# TMC2100_BOB_v0_90.net
KiCad netlist of a schematic drawn in EAGLE
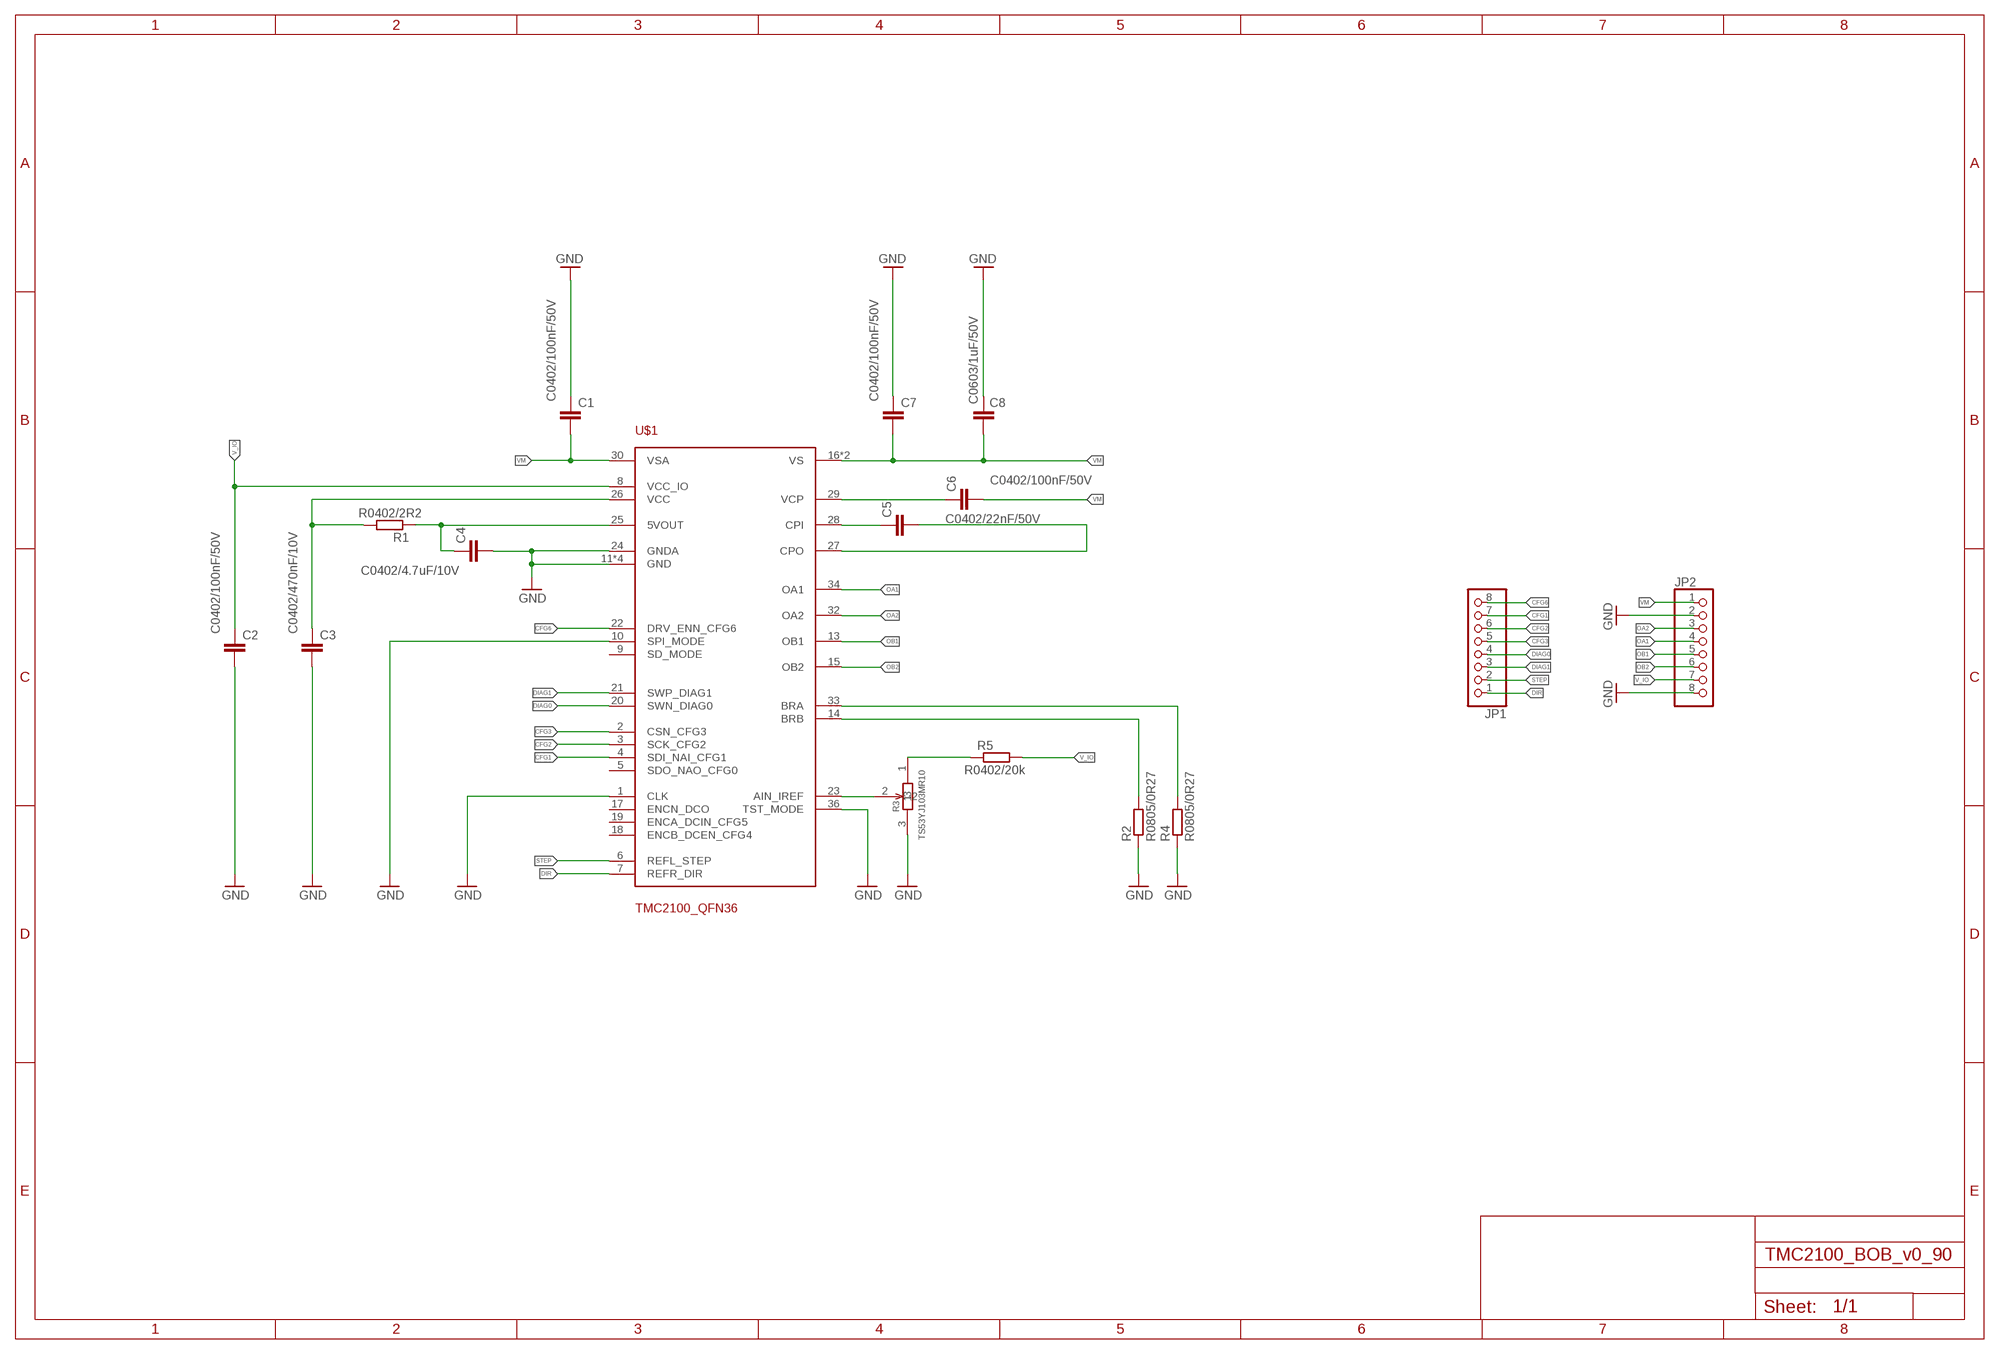
[diagram p0: schematic, sheet 1]

(export (version "E")
  (design (tool "Eeschema 10.0.6"))
  (components
    (comp (ref "C1")
      (value "C0402/100nF/50V")
      (footprint "eagle-import:C0402")
      (libsource (lib "eagle-import") (part "C-EUC0402"))
    )
    (comp (ref "C2")
      (value "C0402/100nF/50V")
      (footprint "eagle-import:C0402")
      (libsource (lib "eagle-import") (part "C-EUC0402"))
    )
    (comp (ref "C3")
      (value "C0402/470nF/10V")
      (footprint "eagle-import:C0402")
      (libsource (lib "eagle-import") (part "C-EUC0402"))
    )
    (comp (ref "C4")
      (value "C0402/4.7uF/10V")
      (footprint "eagle-import:C0402")
      (libsource (lib "eagle-import") (part "C-EUC0402"))
    )
    (comp (ref "C5")
      (value "C0402/22nF/50V")
      (footprint "eagle-import:C0402")
      (libsource (lib "eagle-import") (part "C-EUC0402"))
    )
    (comp (ref "C6")
      (value "C0402/100nF/50V")
      (footprint "eagle-import:C0402")
      (libsource (lib "eagle-import") (part "C-EUC0402"))
    )
    (comp (ref "C7")
      (value "C0402/100nF/50V")
      (footprint "eagle-import:C0402")
      (libsource (lib "eagle-import") (part "C-EUC0402"))
    )
    (comp (ref "C8")
      (value "C0603/1uF/50V")
      (footprint "eagle-import:C0603")
      (libsource (lib "eagle-import") (part "C-EUC0603"))
    )
    (comp (ref "JP1")
      (value "PINHD-1X08_2.54-S")
      (footprint "eagle-import:1X08-S")
      (libsource (lib "eagle-import") (part "PINHD-1X08_2.54-S"))
    )
    (comp (ref "JP2")
      (value "PINHD-1X08_2.54-S")
      (footprint "eagle-import:1X08-S")
      (libsource (lib "eagle-import") (part "PINHD-1X08_2.54-S"))
    )
    (comp (ref "R1")
      (value "R0402/2R2")
      (footprint "eagle-import:R0402")
      (libsource (lib "eagle-import") (part "R-EU_R0402"))
    )
    (comp (ref "R2")
      (value "R0805/0R27")
      (footprint "eagle-import:M0805")
      (libsource (lib "eagle-import") (part "R-EU_M0805"))
    )
    (comp (ref "R3")
      (value "TS53YJ103MR10")
      (footprint "eagle-import:TS53YJ")
      (libsource (lib "eagle-import") (part "TS53YJ103MR10"))
    )
    (comp (ref "R4")
      (value "R0805/0R27")
      (footprint "eagle-import:M0805")
      (libsource (lib "eagle-import") (part "R-EU_M0805"))
    )
    (comp (ref "R5")
      (value "R0402/20k")
      (footprint "eagle-import:R0402")
      (libsource (lib "eagle-import") (part "R-EU_R0402"))
    )
    (comp (ref "U$1")
      (value "TMC2100_QFN36")
      (footprint "eagle-import:QFN36")
      (libsource (lib "eagle-import") (part "TMC2100_QFN36"))
    )
  )
  (nets
    (net (code "1") (name "CFG1") (class "Default")
      (node (ref "JP1") (pin "7") (pinfunction "7_7") (pintype "passive"))
      (node (ref "U$1") (pin "4") (pinfunction "SDI_NAI_CFG1_4") (pintype "bidirectional"))
    )
    (net (code "2") (name "CFG2") (class "Default")
      (node (ref "JP1") (pin "6") (pinfunction "6_6") (pintype "passive"))
      (node (ref "U$1") (pin "3") (pinfunction "SCK_CFG2_3") (pintype "bidirectional"))
    )
    (net (code "3") (name "CFG3") (class "Default")
      (node (ref "JP1") (pin "5") (pinfunction "5_5") (pintype "passive"))
      (node (ref "U$1") (pin "2") (pinfunction "CSN_CFG3_2") (pintype "bidirectional"))
    )
    (net (code "4") (name "CFG6") (class "Default")
      (node (ref "JP1") (pin "8") (pinfunction "8_8") (pintype "passive"))
      (node (ref "U$1") (pin "22") (pinfunction "DRV_ENN_CFG6_22") (pintype "bidirectional"))
    )
    (net (code "5") (name "DIAG0") (class "Default")
      (node (ref "JP1") (pin "4") (pinfunction "4_4") (pintype "passive"))
      (node (ref "U$1") (pin "20") (pinfunction "SWN_DIAG0_20") (pintype "bidirectional"))
    )
    (net (code "6") (name "DIAG1") (class "Default")
      (node (ref "JP1") (pin "3") (pinfunction "3_3") (pintype "passive"))
      (node (ref "U$1") (pin "21") (pinfunction "SWP_DIAG1_21") (pintype "bidirectional"))
    )
    (net (code "7") (name "DIR") (class "Default")
      (node (ref "JP1") (pin "1") (pinfunction "1_1") (pintype "passive"))
      (node (ref "U$1") (pin "7") (pinfunction "REFR_DIR_7") (pintype "bidirectional"))
    )
    (net (code "8") (name "GND") (class "Default")
      (node (ref "C1") (pin "1") (pinfunction "1_1") (pintype "passive"))
      (node (ref "C2") (pin "2") (pinfunction "2_2") (pintype "passive"))
      (node (ref "C3") (pin "2") (pinfunction "2_2") (pintype "passive"))
      (node (ref "C4") (pin "2") (pinfunction "2_2") (pintype "passive"))
      (node (ref "C7") (pin "1") (pinfunction "1_1") (pintype "passive"))
      (node (ref "C8") (pin "2") (pinfunction "2_2") (pintype "passive"))
      (node (ref "JP2") (pin "2") (pinfunction "2_2") (pintype "passive"))
      (node (ref "JP2") (pin "8") (pinfunction "8_8") (pintype "passive"))
      (node (ref "R2") (pin "1") (pinfunction "1_1") (pintype "passive"))
      (node (ref "R3") (pin "3") (pinfunction "3_3") (pintype "bidirectional"))
      (node (ref "R4") (pin "1") (pinfunction "1_1") (pintype "passive"))
      (node (ref "U$1") (pin "1") (pinfunction "CLK_1") (pintype "bidirectional"))
      (node (ref "U$1") (pin "10") (pinfunction "SPI_MODE_10") (pintype "bidirectional"))
      (node (ref "U$1") (pin "11") (pinfunction "GND_11") (pintype "bidirectional"))
      (node (ref "U$1") (pin "12") (pinfunction "GND_12") (pintype "bidirectional"))
      (node (ref "U$1") (pin "24") (pinfunction "GNDA_24") (pintype "bidirectional"))
      (node (ref "U$1") (pin "35") (pinfunction "GND_35") (pintype "bidirectional"))
      (node (ref "U$1") (pin "36") (pinfunction "TST_MODE_36") (pintype "bidirectional"))
      (node (ref "U$1") (pin "GND_PAD") (pinfunction "GND_GND_PAD") (pintype "bidirectional"))
    )
    (net (code "9") (name "Net-(R3-Pad1)") (class "Default")
      (node (ref "R3") (pin "1") (pinfunction "1_1") (pintype "bidirectional"))
      (node (ref "R5") (pin "1") (pinfunction "1_1") (pintype "passive"))
    )
    (net (code "10") (name "Net-(U$1-5VOUT)") (class "Default")
      (node (ref "C4") (pin "1") (pinfunction "1_1") (pintype "passive"))
      (node (ref "R1") (pin "1") (pinfunction "1_1") (pintype "passive"))
      (node (ref "U$1") (pin "25") (pinfunction "5VOUT_25") (pintype "bidirectional"))
    )
    (net (code "11") (name "Net-(U$1-AIN_IREF)") (class "Default")
      (node (ref "R3") (pin "2") (pinfunction "2_2") (pintype "bidirectional"))
      (node (ref "U$1") (pin "23") (pinfunction "AIN_IREF_23") (pintype "bidirectional"))
    )
    (net (code "12") (name "Net-(U$1-BRA)") (class "Default")
      (node (ref "R4") (pin "2") (pinfunction "2_2") (pintype "passive"))
      (node (ref "U$1") (pin "33") (pinfunction "BRA_33") (pintype "bidirectional"))
    )
    (net (code "13") (name "Net-(U$1-BRB)") (class "Default")
      (node (ref "R2") (pin "2") (pinfunction "2_2") (pintype "passive"))
      (node (ref "U$1") (pin "14") (pinfunction "BRB_14") (pintype "bidirectional"))
    )
    (net (code "14") (name "Net-(U$1-CPI)") (class "Default")
      (node (ref "C5") (pin "1") (pinfunction "1_1") (pintype "passive"))
      (node (ref "U$1") (pin "28") (pinfunction "CPI_28") (pintype "bidirectional"))
    )
    (net (code "15") (name "Net-(U$1-CPO)") (class "Default")
      (node (ref "C5") (pin "2") (pinfunction "2_2") (pintype "passive"))
      (node (ref "U$1") (pin "27") (pinfunction "CPO_27") (pintype "bidirectional"))
    )
    (net (code "16") (name "Net-(U$1-VCC)") (class "Default")
      (node (ref "C3") (pin "1") (pinfunction "1_1") (pintype "passive"))
      (node (ref "R1") (pin "2") (pinfunction "2_2") (pintype "passive"))
      (node (ref "U$1") (pin "26") (pinfunction "VCC_26") (pintype "bidirectional"))
    )
    (net (code "17") (name "Net-(U$1-VCP)") (class "Default")
      (node (ref "C6") (pin "1") (pinfunction "1_1") (pintype "passive"))
      (node (ref "U$1") (pin "29") (pinfunction "VCP_29") (pintype "bidirectional"))
    )
    (net (code "18") (name "OA1") (class "Default")
      (node (ref "JP2") (pin "4") (pinfunction "4_4") (pintype "passive"))
      (node (ref "U$1") (pin "34") (pinfunction "OA1_34") (pintype "bidirectional"))
    )
    (net (code "19") (name "OA2") (class "Default")
      (node (ref "JP2") (pin "3") (pinfunction "3_3") (pintype "passive"))
      (node (ref "U$1") (pin "32") (pinfunction "OA2_32") (pintype "bidirectional"))
    )
    (net (code "20") (name "OB1") (class "Default")
      (node (ref "JP2") (pin "5") (pinfunction "5_5") (pintype "passive"))
      (node (ref "U$1") (pin "13") (pinfunction "OB1_13") (pintype "bidirectional"))
    )
    (net (code "21") (name "OB2") (class "Default")
      (node (ref "JP2") (pin "6") (pinfunction "6_6") (pintype "passive"))
      (node (ref "U$1") (pin "15") (pinfunction "OB2_15") (pintype "bidirectional"))
    )
    (net (code "22") (name "STEP") (class "Default")
      (node (ref "JP1") (pin "2") (pinfunction "2_2") (pintype "passive"))
      (node (ref "U$1") (pin "6") (pinfunction "REFL_STEP_6") (pintype "bidirectional"))
    )
    (net (code "23") (name "VM") (class "Default")
      (node (ref "C1") (pin "2") (pinfunction "2_2") (pintype "passive"))
      (node (ref "C6") (pin "2") (pinfunction "2_2") (pintype "passive"))
      (node (ref "C7") (pin "2") (pinfunction "2_2") (pintype "passive"))
      (node (ref "C8") (pin "1") (pinfunction "1_1") (pintype "passive"))
      (node (ref "JP2") (pin "1") (pinfunction "1_1") (pintype "passive"))
      (node (ref "U$1") (pin "16") (pinfunction "VS_16") (pintype "bidirectional"))
      (node (ref "U$1") (pin "30") (pinfunction "VSA_30") (pintype "bidirectional"))
      (node (ref "U$1") (pin "31") (pinfunction "VS_31") (pintype "bidirectional"))
    )
    (net (code "24") (name "V_IO") (class "Default")
      (node (ref "C2") (pin "1") (pinfunction "1_1") (pintype "passive"))
      (node (ref "JP2") (pin "7") (pinfunction "7_7") (pintype "passive"))
      (node (ref "R5") (pin "2") (pinfunction "2_2") (pintype "passive"))
      (node (ref "U$1") (pin "8") (pinfunction "VCC_IO_8") (pintype "bidirectional"))
    )
    (net (code "25") (name "unconnected-(U$1-ENCA_DCIN_CFG5-Pad19)") (class "Default")
      (node (ref "U$1") (pin "19") (pinfunction "ENCA_DCIN_CFG5_19") (pintype "bidirectional"))
    )
    (net (code "26") (name "unconnected-(U$1-ENCB_DCEN_CFG4-Pad18)") (class "Default")
      (node (ref "U$1") (pin "18") (pinfunction "ENCB_DCEN_CFG4_18") (pintype "bidirectional"))
    )
    (net (code "27") (name "unconnected-(U$1-ENCN_DCO-Pad17)") (class "Default")
      (node (ref "U$1") (pin "17") (pinfunction "ENCN_DCO_17") (pintype "bidirectional"))
    )
    (net (code "28") (name "unconnected-(U$1-SDO_NAO_CFG0-Pad5)") (class "Default")
      (node (ref "U$1") (pin "5") (pinfunction "SDO_NAO_CFG0_5") (pintype "bidirectional"))
    )
    (net (code "29") (name "unconnected-(U$1-SD_MODE-Pad9)") (class "Default")
      (node (ref "U$1") (pin "9") (pinfunction "SD_MODE_9") (pintype "bidirectional"))
    )
  )
)
